# BreakoutBoard_RevA.net
KiCad netlist of a schematic drawn in EAGLE
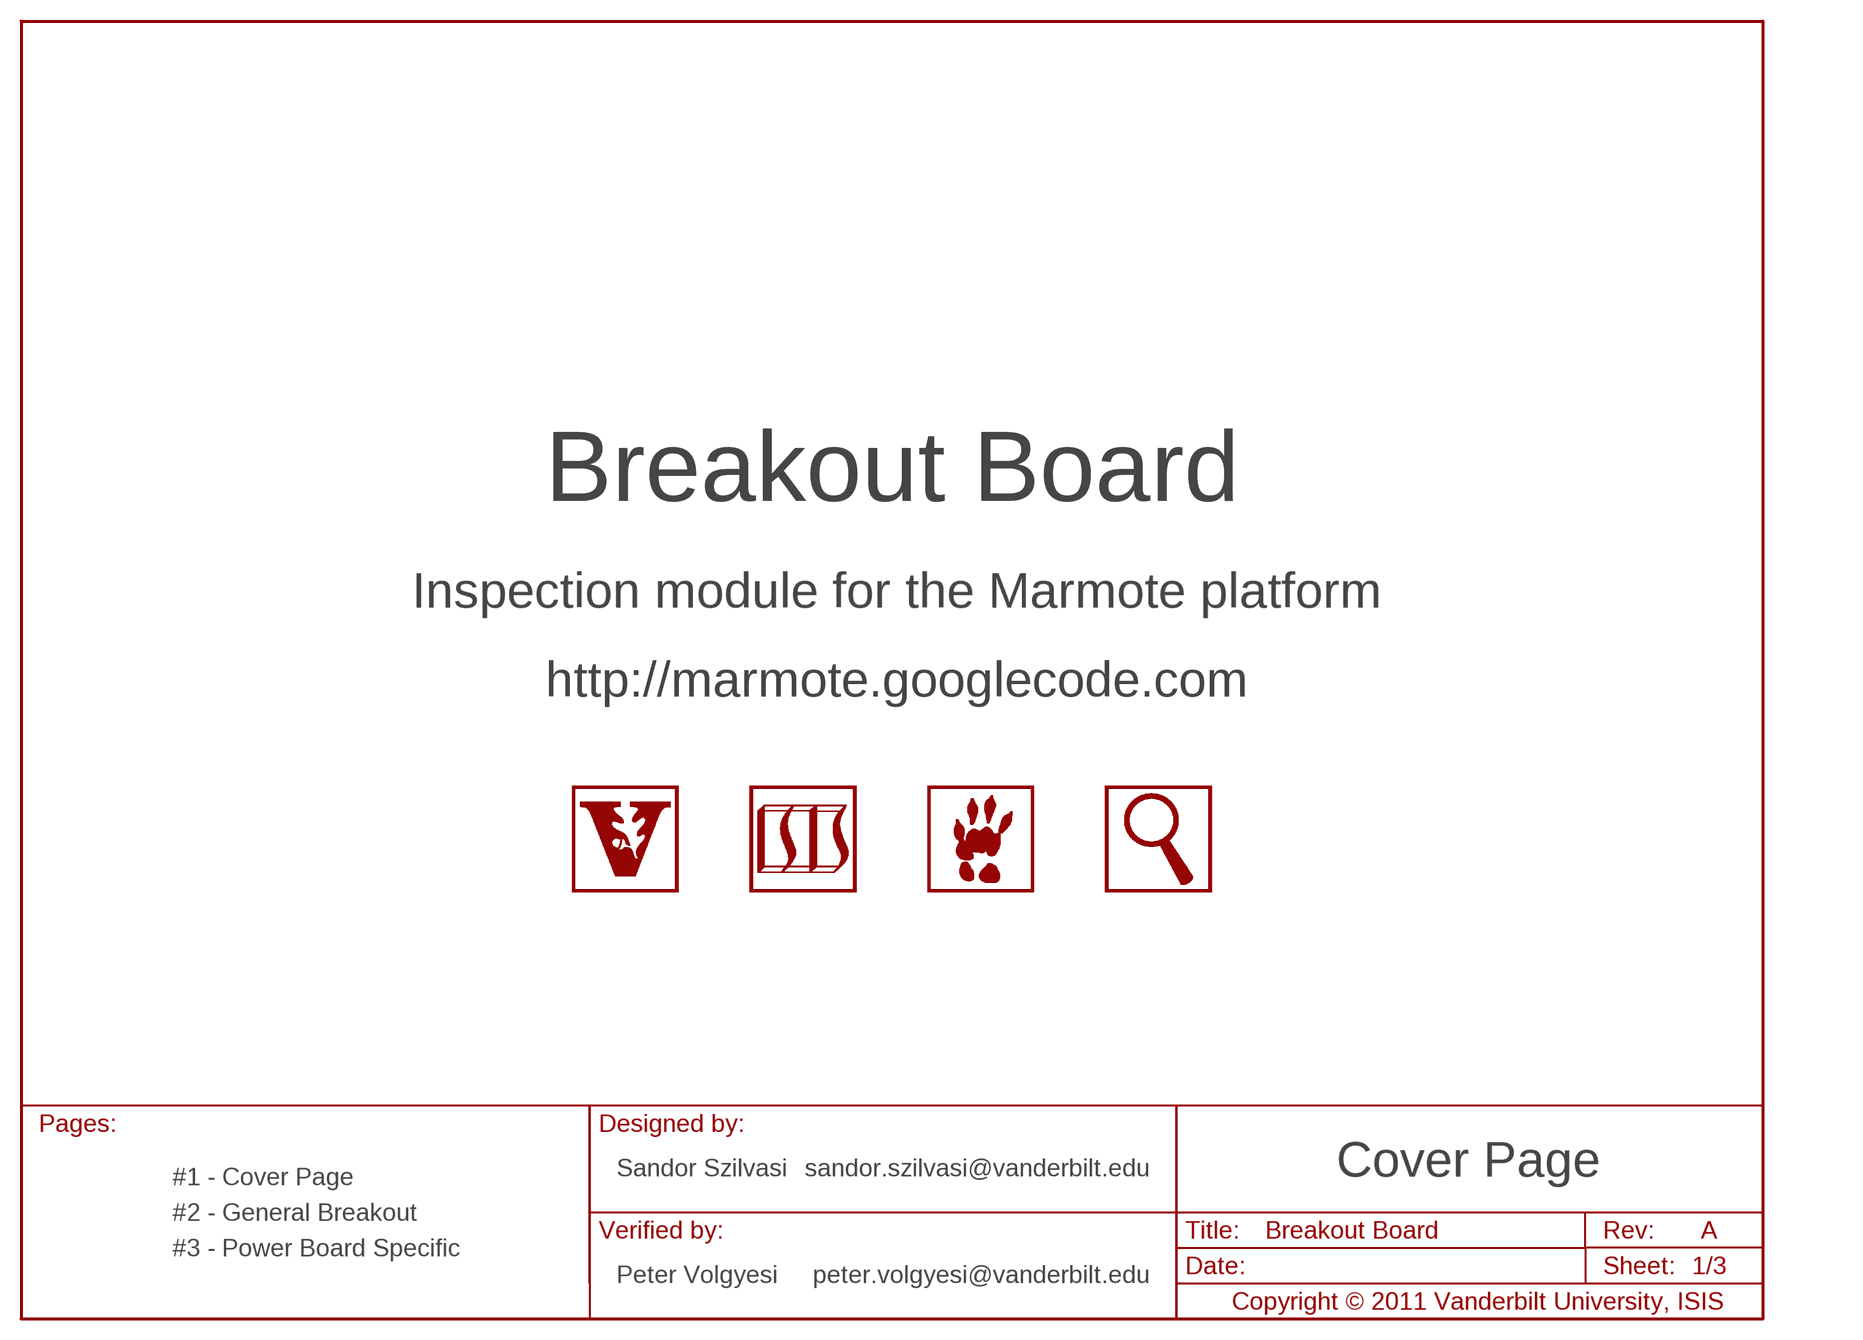
[diagram p0: schematic, sheet 1]
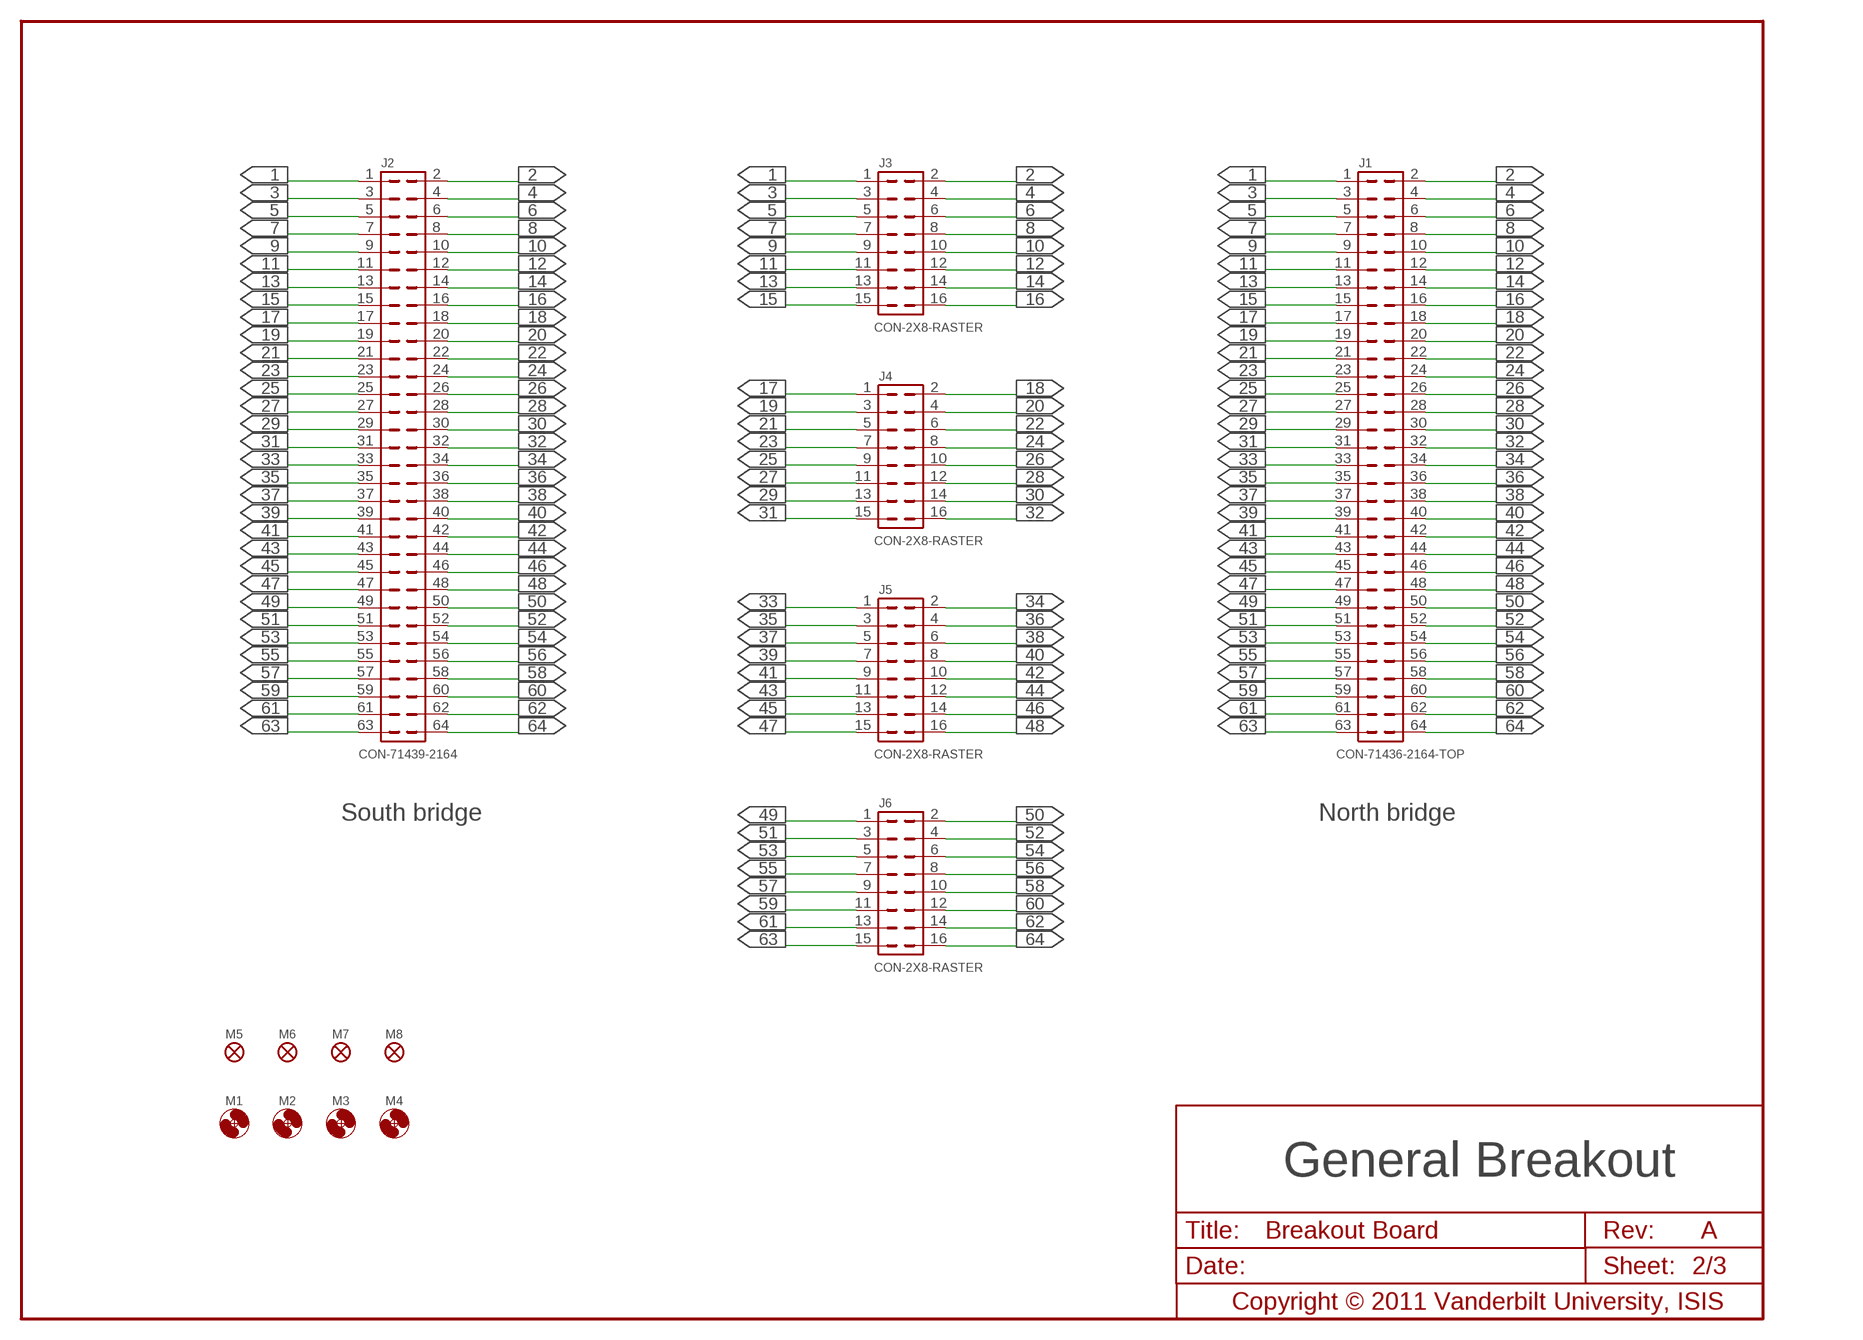
[diagram p1: schematic, sheet 2]
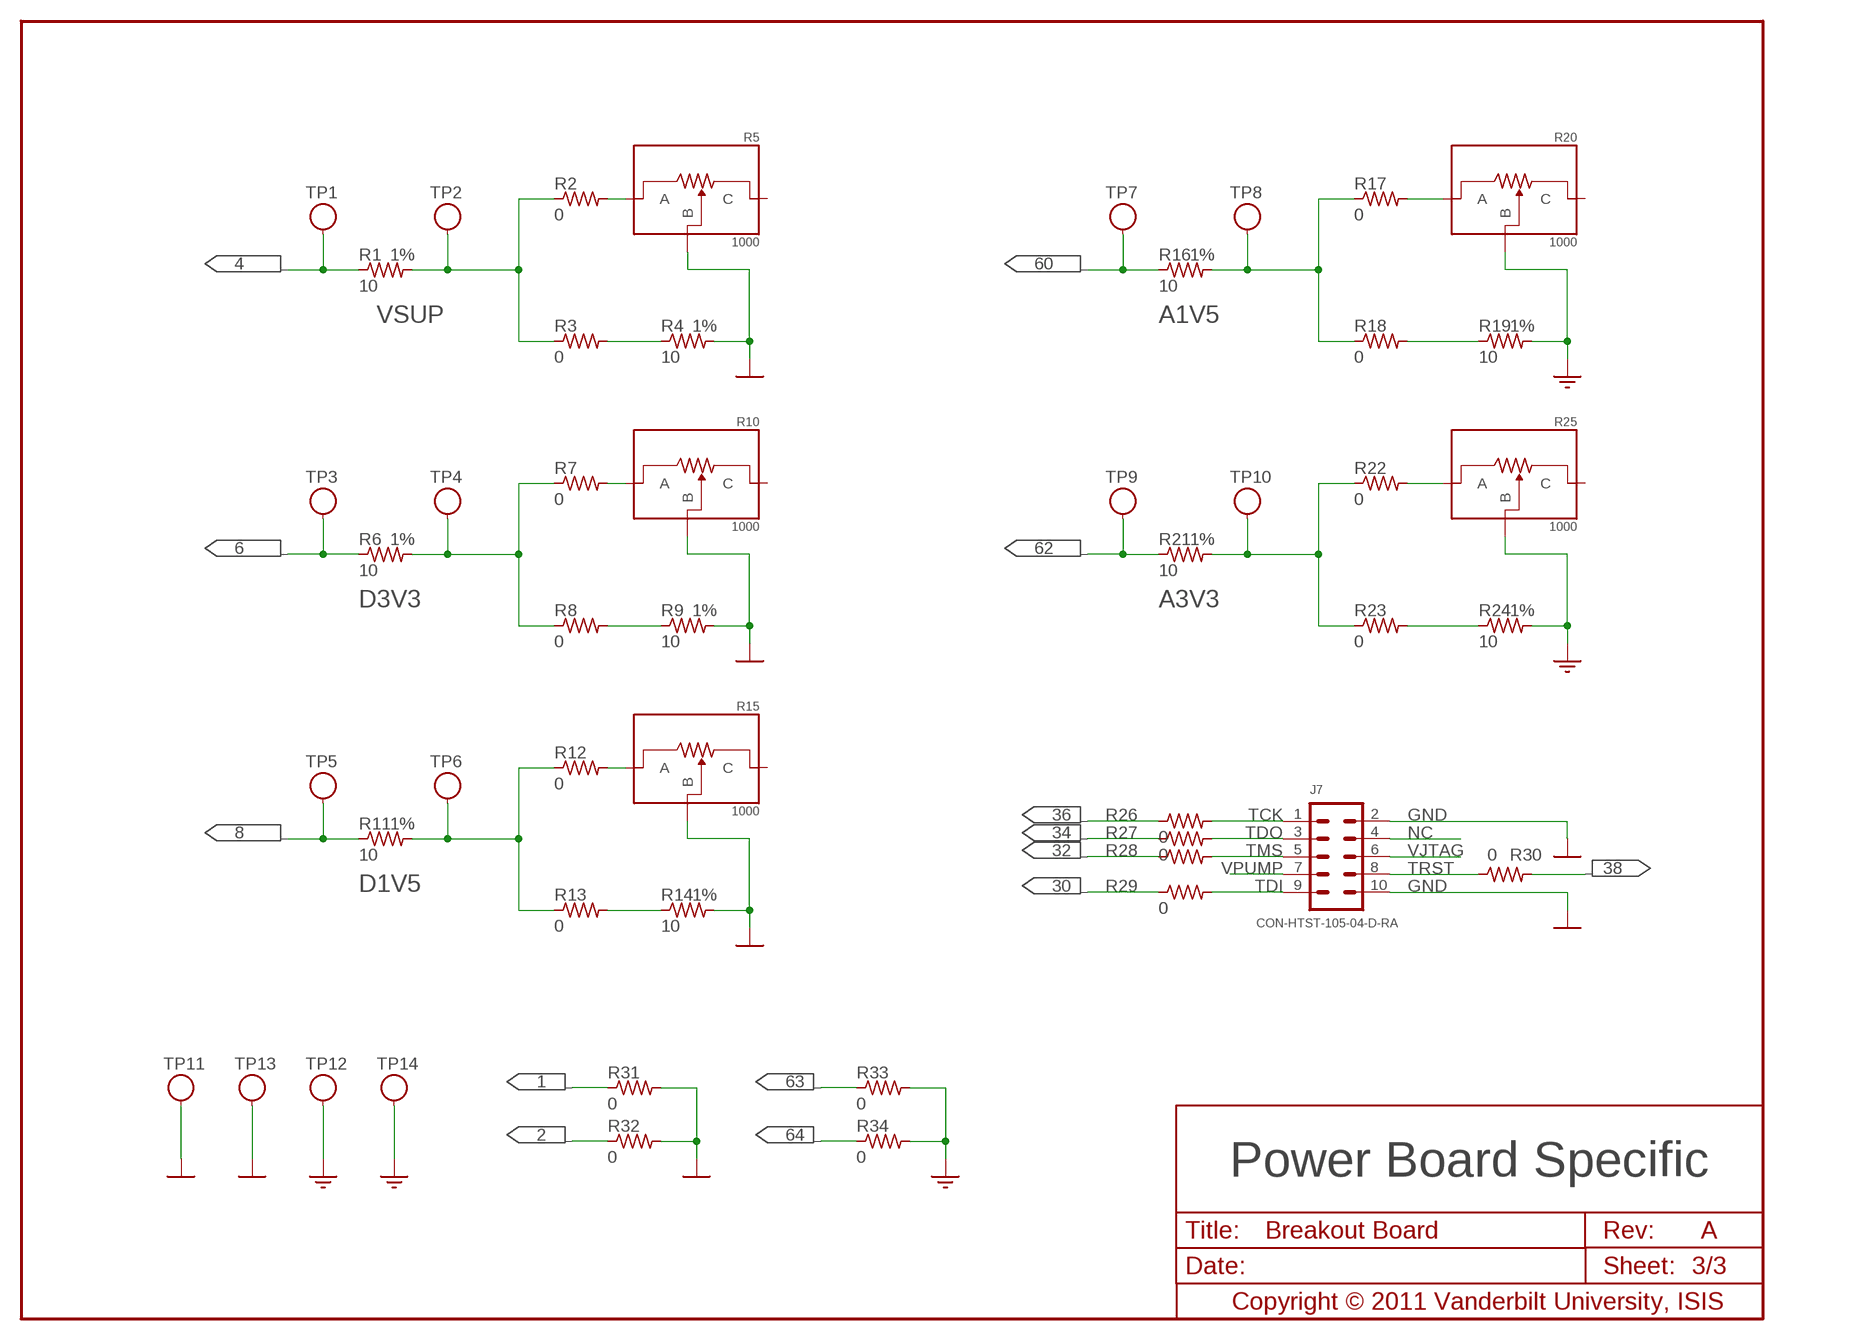
[diagram p2: schematic, sheet 3]

(export (version "E")
  (design (tool "Eeschema 10.0.6"))
  (components
    (comp (ref "J7")
      (value "CON-HTST-105-04-D-RA")
      (footprint "eagle-import:HTST-105-04-D-RA")
      (libsource (lib "eagle-import") (part "CON-HTST-105-04-D-RA"))
    )
    (comp (ref "R1")
      (value "10")
      (footprint "eagle-import:R0805")
      (fields (field (name "TOLERANCE") "1%"))
      (libsource (lib "eagle-import") (part "R0805"))
    )
    (comp (ref "R2")
      (value "0")
      (footprint "eagle-import:R0805")
      (libsource (lib "eagle-import") (part "R0805"))
    )
    (comp (ref "R3")
      (value "0")
      (footprint "eagle-import:R0805")
      (libsource (lib "eagle-import") (part "R0805"))
    )
    (comp (ref "R4")
      (value "10")
      (footprint "eagle-import:R0805")
      (fields (field (name "TOLERANCE") "1%"))
      (libsource (lib "eagle-import") (part "R0805"))
    )
    (comp (ref "R5")
      (value "1000")
      (footprint "eagle-import:TRIMMER-3MM")
      (fields (field (name "MF") "Panasonic - ECG") (field (name "MPN") "EVM-3WSX80B13 "))
      (libsource (lib "eagle-import") (part "TRIMMER"))
    )
    (comp (ref "R6")
      (value "10")
      (footprint "eagle-import:R0805")
      (fields (field (name "TOLERANCE") "1%"))
      (libsource (lib "eagle-import") (part "R0805"))
    )
    (comp (ref "R7")
      (value "0")
      (footprint "eagle-import:R0805")
      (libsource (lib "eagle-import") (part "R0805"))
    )
    (comp (ref "R8")
      (value "0")
      (footprint "eagle-import:R0805")
      (libsource (lib "eagle-import") (part "R0805"))
    )
    (comp (ref "R9")
      (value "10")
      (footprint "eagle-import:R0805")
      (fields (field (name "TOLERANCE") "1%"))
      (libsource (lib "eagle-import") (part "R0805"))
    )
    (comp (ref "R10")
      (value "1000")
      (footprint "eagle-import:TRIMMER-3MM")
      (fields (field (name "MF") "Panasonic - ECG") (field (name "MPN") "EVM-3WSX80B13 "))
      (libsource (lib "eagle-import") (part "TRIMMER"))
    )
    (comp (ref "R11")
      (value "10")
      (footprint "eagle-import:R0805")
      (fields (field (name "TOLERANCE") "1%"))
      (libsource (lib "eagle-import") (part "R0805"))
    )
    (comp (ref "R12")
      (value "0")
      (footprint "eagle-import:R0805")
      (libsource (lib "eagle-import") (part "R0805"))
    )
    (comp (ref "R13")
      (value "0")
      (footprint "eagle-import:R0805")
      (libsource (lib "eagle-import") (part "R0805"))
    )
    (comp (ref "R14")
      (value "10")
      (footprint "eagle-import:R0805")
      (fields (field (name "TOLERANCE") "1%"))
      (libsource (lib "eagle-import") (part "R0805"))
    )
    (comp (ref "R15")
      (value "1000")
      (footprint "eagle-import:TRIMMER-3MM")
      (fields (field (name "MF") "Panasonic - ECG") (field (name "MPN") "EVM-3WSX80B13 "))
      (libsource (lib "eagle-import") (part "TRIMMER"))
    )
    (comp (ref "R16")
      (value "10")
      (footprint "eagle-import:R0805")
      (fields (field (name "TOLERANCE") "1%"))
      (libsource (lib "eagle-import") (part "R0805"))
    )
    (comp (ref "R17")
      (value "0")
      (footprint "eagle-import:R0805")
      (libsource (lib "eagle-import") (part "R0805"))
    )
    (comp (ref "R18")
      (value "0")
      (footprint "eagle-import:R0805")
      (libsource (lib "eagle-import") (part "R0805"))
    )
    (comp (ref "R19")
      (value "10")
      (footprint "eagle-import:R0805")
      (fields (field (name "TOLERANCE") "1%"))
      (libsource (lib "eagle-import") (part "R0805"))
    )
    (comp (ref "R20")
      (value "1000")
      (footprint "eagle-import:TRIMMER-3MM")
      (fields (field (name "MF") "Panasonic - ECG") (field (name "MPN") "EVM-3WSX80B13 "))
      (libsource (lib "eagle-import") (part "TRIMMER"))
    )
    (comp (ref "R21")
      (value "10")
      (footprint "eagle-import:R0805")
      (fields (field (name "TOLERANCE") "1%"))
      (libsource (lib "eagle-import") (part "R0805"))
    )
    (comp (ref "R22")
      (value "0")
      (footprint "eagle-import:R0805")
      (libsource (lib "eagle-import") (part "R0805"))
    )
    (comp (ref "R23")
      (value "0")
      (footprint "eagle-import:R0805")
      (libsource (lib "eagle-import") (part "R0805"))
    )
    (comp (ref "R24")
      (value "10")
      (footprint "eagle-import:R0805")
      (fields (field (name "TOLERANCE") "1%"))
      (libsource (lib "eagle-import") (part "R0805"))
    )
    (comp (ref "R25")
      (value "1000")
      (footprint "eagle-import:TRIMMER-3MM")
      (fields (field (name "MF") "Panasonic - ECG") (field (name "MPN") "EVM-3WSX80B13 "))
      (libsource (lib "eagle-import") (part "TRIMMER"))
    )
    (comp (ref "R26")
      (value "0")
      (footprint "eagle-import:R0805")
      (libsource (lib "eagle-import") (part "R0805"))
    )
    (comp (ref "R27")
      (value "0")
      (footprint "eagle-import:R0805")
      (libsource (lib "eagle-import") (part "R0805"))
    )
    (comp (ref "R28")
      (value "0")
      (footprint "eagle-import:R0805")
      (libsource (lib "eagle-import") (part "R0805"))
    )
    (comp (ref "R29")
      (value "0")
      (footprint "eagle-import:R0805")
      (libsource (lib "eagle-import") (part "R0805"))
    )
    (comp (ref "R30")
      (value "0")
      (footprint "eagle-import:R0805")
      (libsource (lib "eagle-import") (part "R0805"))
    )
    (comp (ref "R31")
      (value "0")
      (footprint "eagle-import:R0805")
      (libsource (lib "eagle-import") (part "R0805"))
    )
    (comp (ref "R32")
      (value "0")
      (footprint "eagle-import:R0805")
      (libsource (lib "eagle-import") (part "R0805"))
    )
    (comp (ref "R33")
      (value "0")
      (footprint "eagle-import:R0805")
      (libsource (lib "eagle-import") (part "R0805"))
    )
    (comp (ref "R34")
      (value "0")
      (footprint "eagle-import:R0805")
      (libsource (lib "eagle-import") (part "R0805"))
    )
    (comp (ref "TP1")
      (value "TESTPOINT-BLUE")
      (footprint "eagle-import:TESTPOINT")
      (fields (field (name "MF") "Keystone") (field (name "MPN") "5122"))
      (libsource (lib "eagle-import") (part "TESTPOINT-BLUE"))
    )
    (comp (ref "TP2")
      (value "TESTPOINT-BLUE")
      (footprint "eagle-import:TESTPOINT")
      (fields (field (name "MF") "Keystone") (field (name "MPN") "5122"))
      (libsource (lib "eagle-import") (part "TESTPOINT-BLUE"))
    )
    (comp (ref "TP3")
      (value "TESTPOINT-BLUE")
      (footprint "eagle-import:TESTPOINT")
      (fields (field (name "MF") "Keystone") (field (name "MPN") "5122"))
      (libsource (lib "eagle-import") (part "TESTPOINT-BLUE"))
    )
    (comp (ref "TP4")
      (value "TESTPOINT-BLUE")
      (footprint "eagle-import:TESTPOINT")
      (fields (field (name "MF") "Keystone") (field (name "MPN") "5122"))
      (libsource (lib "eagle-import") (part "TESTPOINT-BLUE"))
    )
    (comp (ref "TP5")
      (value "TESTPOINT-BLUE")
      (footprint "eagle-import:TESTPOINT")
      (fields (field (name "MF") "Keystone") (field (name "MPN") "5122"))
      (libsource (lib "eagle-import") (part "TESTPOINT-BLUE"))
    )
    (comp (ref "TP6")
      (value "TESTPOINT-BLUE")
      (footprint "eagle-import:TESTPOINT")
      (fields (field (name "MF") "Keystone") (field (name "MPN") "5122"))
      (libsource (lib "eagle-import") (part "TESTPOINT-BLUE"))
    )
    (comp (ref "TP7")
      (value "TESTPOINT-GREEN")
      (footprint "eagle-import:TESTPOINT")
      (fields (field (name "MF") "Keystone") (field (name "MPN") "5121"))
      (libsource (lib "eagle-import") (part "TESTPOINT-GREEN"))
    )
    (comp (ref "TP8")
      (value "TESTPOINT-GREEN")
      (footprint "eagle-import:TESTPOINT")
      (fields (field (name "MF") "Keystone") (field (name "MPN") "5121"))
      (libsource (lib "eagle-import") (part "TESTPOINT-GREEN"))
    )
    (comp (ref "TP9")
      (value "TESTPOINT-GREEN")
      (footprint "eagle-import:TESTPOINT")
      (fields (field (name "MF") "Keystone") (field (name "MPN") "5121"))
      (libsource (lib "eagle-import") (part "TESTPOINT-GREEN"))
    )
    (comp (ref "TP10")
      (value "TESTPOINT-GREEN")
      (footprint "eagle-import:TESTPOINT")
      (fields (field (name "MF") "Keystone") (field (name "MPN") "5121"))
      (libsource (lib "eagle-import") (part "TESTPOINT-GREEN"))
    )
    (comp (ref "TP11")
      (value "TESTPOINT-YELLOW")
      (footprint "eagle-import:TESTPOINT")
      (fields (field (name "MF") "Keystone") (field (name "MPN") "5009"))
      (libsource (lib "eagle-import") (part "TESTPOINT-YELLOW"))
    )
    (comp (ref "TP12")
      (value "TESTPOINT-YELLOW")
      (footprint "eagle-import:TESTPOINT")
      (fields (field (name "MF") "Keystone") (field (name "MPN") "5009"))
      (libsource (lib "eagle-import") (part "TESTPOINT-YELLOW"))
    )
    (comp (ref "TP13")
      (value "TESTPOINT-YELLOW")
      (footprint "eagle-import:TESTPOINT")
      (fields (field (name "MF") "Keystone") (field (name "MPN") "5009"))
      (libsource (lib "eagle-import") (part "TESTPOINT-YELLOW"))
    )
    (comp (ref "TP14")
      (value "TESTPOINT-YELLOW")
      (footprint "eagle-import:TESTPOINT")
      (fields (field (name "MF") "Keystone") (field (name "MPN") "5009"))
      (libsource (lib "eagle-import") (part "TESTPOINT-YELLOW"))
    )
    (comp (ref "J1")
      (value "CON-71436-2164-TOP")
      (footprint "eagle-import:71436-XX64")
      (fields (field (name "MF") "Molex") (field (name "MPN") "71436-2164"))
      (libsource (lib "eagle-import") (part "CON-7143664-TOP-21"))
    )
    (comp (ref "J2")
      (value "CON-71439-2164")
      (footprint "eagle-import:71439-XX64-BOT")
      (fields (field (name "MF") "Molex") (field (name "MPN") "71439-2164"))
      (libsource (lib "eagle-import") (part "CON-7143964-21"))
    )
    (comp (ref "J3")
      (value "CON-2X8-RASTER")
      (footprint "eagle-import:2X16")
      (libsource (lib "eagle-import") (part "CON-2X8-RASTER"))
    )
    (comp (ref "J4")
      (value "CON-2X8-RASTER")
      (footprint "eagle-import:2X16")
      (libsource (lib "eagle-import") (part "CON-2X8-RASTER"))
    )
    (comp (ref "J5")
      (value "CON-2X8-RASTER")
      (footprint "eagle-import:2X16")
      (libsource (lib "eagle-import") (part "CON-2X8-RASTER"))
    )
    (comp (ref "J6")
      (value "CON-2X8-RASTER")
      (footprint "eagle-import:2X16")
      (libsource (lib "eagle-import") (part "CON-2X8-RASTER"))
    )
    (comp (ref "M1")
      (value "MOUNT-HOLE3.3")
      (footprint "eagle-import:3,3")
      (libsource (lib "eagle-import") (part "MOUNT-HOLE3.3"))
    )
    (comp (ref "M2")
      (value "MOUNT-HOLE3.3")
      (footprint "eagle-import:3,3")
      (libsource (lib "eagle-import") (part "MOUNT-HOLE3.3"))
    )
    (comp (ref "M3")
      (value "MOUNT-HOLE3.3")
      (footprint "eagle-import:3,3")
      (libsource (lib "eagle-import") (part "MOUNT-HOLE3.3"))
    )
    (comp (ref "M4")
      (value "MOUNT-HOLE3.3")
      (footprint "eagle-import:3,3")
      (libsource (lib "eagle-import") (part "MOUNT-HOLE3.3"))
    )
    (comp (ref "M5")
      (value "FIDUCIAL1X2")
      (footprint "eagle-import:FIDUCIAL-1X2")
      (libsource (lib "eagle-import") (part "FIDUCIAL1X2"))
    )
    (comp (ref "M6")
      (value "FIDUCIAL1X2")
      (footprint "eagle-import:FIDUCIAL-1X2")
      (libsource (lib "eagle-import") (part "FIDUCIAL1X2"))
    )
    (comp (ref "M7")
      (value "FIDUCIAL1X2")
      (footprint "eagle-import:FIDUCIAL-1X2")
      (libsource (lib "eagle-import") (part "FIDUCIAL1X2"))
    )
    (comp (ref "M8")
      (value "FIDUCIAL1X2")
      (footprint "eagle-import:FIDUCIAL-1X2")
      (libsource (lib "eagle-import") (part "FIDUCIAL1X2"))
    )
    (comp (ref "LOGO1")
      (value "LOGO-ISIS-600MIL-10MM-AU")
      (footprint "eagle-import:LOGO-ISIS-10MM-GOLD")
      (libsource (lib "eagle-import") (part "LOGO-ISIS-600MIL-10MM-AU"))
    )
    (comp (ref "LOGO2")
      (value "LOGO-VANDERBILT-600MIL-10MM-AU")
      (footprint "eagle-import:LOGO-VANDERBILT-10MM-GOLD")
      (libsource (lib "eagle-import") (part "LOGO-VANDERBILT-600MIL-10MM-AU"))
    )
    (comp (ref "LOGO3")
      (value "LOGO-MARMOTE-600MIL-10MM-AU")
      (footprint "eagle-import:LOGO-MARMOTE-10MM-GOLD")
      (libsource (lib "eagle-import") (part "LOGO-MARMOTE-600MIL-10MM-AU"))
    )
    (comp (ref "LOGO4")
      (value "LOGO-MAGNIFYING-GLASS-600MIL-10MM-AU")
      (footprint "eagle-import:LOGO-MAGNIFYING-GLASS-10MM-GOLD")
      (libsource (lib "eagle-import") (part "LOGO-MAGNIFYING-GLASS-600MIL-10MM-AU"))
    )
  )
  (nets
    (net (code "1") (name "1") (class "Default")
      (node (ref "J1") (pin "1") (pinfunction "1_1") (pintype "passive"))
      (node (ref "J2") (pin "1") (pinfunction "1_1") (pintype "passive"))
      (node (ref "J3") (pin "1") (pinfunction "1_1") (pintype "passive"))
      (node (ref "R31") (pin "1") (pinfunction "1_1") (pintype "passive"))
    )
    (net (code "2") (name "2") (class "Default")
      (node (ref "J1") (pin "2") (pinfunction "2_2") (pintype "passive"))
      (node (ref "J2") (pin "2") (pinfunction "2_2") (pintype "passive"))
      (node (ref "J3") (pin "2") (pinfunction "2_2") (pintype "passive"))
      (node (ref "R32") (pin "1") (pinfunction "1_1") (pintype "passive"))
    )
    (net (code "3") (name "3") (class "Default")
      (node (ref "J1") (pin "3") (pinfunction "3_3") (pintype "passive"))
      (node (ref "J2") (pin "3") (pinfunction "3_3") (pintype "passive"))
      (node (ref "J3") (pin "3") (pinfunction "3_3") (pintype "passive"))
    )
    (net (code "4") (name "4") (class "Default")
      (node (ref "J1") (pin "4") (pinfunction "4_4") (pintype "passive"))
      (node (ref "J2") (pin "4") (pinfunction "4_4") (pintype "passive"))
      (node (ref "J3") (pin "4") (pinfunction "4_4") (pintype "passive"))
      (node (ref "R1") (pin "1") (pinfunction "1_1") (pintype "passive"))
      (node (ref "TP1") (pin "1") (pinfunction "1_1") (pintype "power_in"))
    )
    (net (code "5") (name "5") (class "Default")
      (node (ref "J1") (pin "5") (pinfunction "5_5") (pintype "passive"))
      (node (ref "J2") (pin "5") (pinfunction "5_5") (pintype "passive"))
      (node (ref "J3") (pin "5") (pinfunction "5_5") (pintype "passive"))
    )
    (net (code "6") (name "6") (class "Default")
      (node (ref "J1") (pin "6") (pinfunction "6_6") (pintype "passive"))
      (node (ref "J2") (pin "6") (pinfunction "6_6") (pintype "passive"))
      (node (ref "J3") (pin "6") (pinfunction "6_6") (pintype "passive"))
      (node (ref "R6") (pin "1") (pinfunction "1_1") (pintype "passive"))
      (node (ref "TP3") (pin "1") (pinfunction "1_1") (pintype "power_in"))
    )
    (net (code "7") (name "7") (class "Default")
      (node (ref "J1") (pin "7") (pinfunction "7_7") (pintype "passive"))
      (node (ref "J2") (pin "7") (pinfunction "7_7") (pintype "passive"))
      (node (ref "J3") (pin "7") (pinfunction "7_7") (pintype "passive"))
    )
    (net (code "8") (name "8") (class "Default")
      (node (ref "J1") (pin "8") (pinfunction "8_8") (pintype "passive"))
      (node (ref "J2") (pin "8") (pinfunction "8_8") (pintype "passive"))
      (node (ref "J3") (pin "8") (pinfunction "8_8") (pintype "passive"))
      (node (ref "R11") (pin "1") (pinfunction "1_1") (pintype "passive"))
      (node (ref "TP5") (pin "1") (pinfunction "1_1") (pintype "power_in"))
    )
    (net (code "9") (name "9") (class "Default")
      (node (ref "J1") (pin "9") (pinfunction "9_9") (pintype "passive"))
      (node (ref "J2") (pin "9") (pinfunction "9_9") (pintype "passive"))
      (node (ref "J3") (pin "9") (pinfunction "9_9") (pintype "passive"))
    )
    (net (code "10") (name "10") (class "Default")
      (node (ref "J1") (pin "10") (pinfunction "10_10") (pintype "passive"))
      (node (ref "J2") (pin "10") (pinfunction "10_10") (pintype "passive"))
      (node (ref "J3") (pin "10") (pinfunction "10_10") (pintype "passive"))
    )
    (net (code "11") (name "11") (class "Default")
      (node (ref "J1") (pin "11") (pinfunction "11_11") (pintype "passive"))
      (node (ref "J2") (pin "11") (pinfunction "11_11") (pintype "passive"))
      (node (ref "J3") (pin "11") (pinfunction "11_11") (pintype "passive"))
    )
    (net (code "12") (name "12") (class "Default")
      (node (ref "J1") (pin "12") (pinfunction "12_12") (pintype "passive"))
      (node (ref "J2") (pin "12") (pinfunction "12_12") (pintype "passive"))
      (node (ref "J3") (pin "12") (pinfunction "12_12") (pintype "passive"))
    )
    (net (code "13") (name "13") (class "Default")
      (node (ref "J1") (pin "13") (pinfunction "13_13") (pintype "passive"))
      (node (ref "J2") (pin "13") (pinfunction "13_13") (pintype "passive"))
      (node (ref "J3") (pin "13") (pinfunction "13_13") (pintype "passive"))
    )
    (net (code "14") (name "14") (class "Default")
      (node (ref "J1") (pin "14") (pinfunction "14_14") (pintype "passive"))
      (node (ref "J2") (pin "14") (pinfunction "14_14") (pintype "passive"))
      (node (ref "J3") (pin "14") (pinfunction "14_14") (pintype "passive"))
    )
    (net (code "15") (name "15") (class "Default")
      (node (ref "J1") (pin "15") (pinfunction "15_15") (pintype "passive"))
      (node (ref "J2") (pin "15") (pinfunction "15_15") (pintype "passive"))
      (node (ref "J3") (pin "15") (pinfunction "15_15") (pintype "passive"))
    )
    (net (code "16") (name "16") (class "Default")
      (node (ref "J1") (pin "16") (pinfunction "16_16") (pintype "passive"))
      (node (ref "J2") (pin "16") (pinfunction "16_16") (pintype "passive"))
      (node (ref "J3") (pin "16") (pinfunction "16_16") (pintype "passive"))
    )
    (net (code "17") (name "17") (class "Default")
      (node (ref "J1") (pin "17") (pinfunction "17_17") (pintype "passive"))
      (node (ref "J2") (pin "17") (pinfunction "17_17") (pintype "passive"))
      (node (ref "J4") (pin "1") (pinfunction "1_1") (pintype "passive"))
    )
    (net (code "18") (name "18") (class "Default")
      (node (ref "J1") (pin "18") (pinfunction "18_18") (pintype "passive"))
      (node (ref "J2") (pin "18") (pinfunction "18_18") (pintype "passive"))
      (node (ref "J4") (pin "2") (pinfunction "2_2") (pintype "passive"))
    )
    (net (code "19") (name "19") (class "Default")
      (node (ref "J1") (pin "19") (pinfunction "19_19") (pintype "passive"))
      (node (ref "J2") (pin "19") (pinfunction "19_19") (pintype "passive"))
      (node (ref "J4") (pin "3") (pinfunction "3_3") (pintype "passive"))
    )
    (net (code "20") (name "20") (class "Default")
      (node (ref "J1") (pin "20") (pinfunction "20_20") (pintype "passive"))
      (node (ref "J2") (pin "20") (pinfunction "20_20") (pintype "passive"))
      (node (ref "J4") (pin "4") (pinfunction "4_4") (pintype "passive"))
    )
    (net (code "21") (name "21") (class "Default")
      (node (ref "J1") (pin "21") (pinfunction "21_21") (pintype "passive"))
      (node (ref "J2") (pin "21") (pinfunction "21_21") (pintype "passive"))
      (node (ref "J4") (pin "5") (pinfunction "5_5") (pintype "passive"))
    )
    (net (code "22") (name "22") (class "Default")
      (node (ref "J1") (pin "22") (pinfunction "22_22") (pintype "passive"))
      (node (ref "J2") (pin "22") (pinfunction "22_22") (pintype "passive"))
      (node (ref "J4") (pin "6") (pinfunction "6_6") (pintype "passive"))
    )
    (net (code "23") (name "23") (class "Default")
      (node (ref "J1") (pin "23") (pinfunction "23_23") (pintype "passive"))
      (node (ref "J2") (pin "23") (pinfunction "23_23") (pintype "passive"))
      (node (ref "J4") (pin "7") (pinfunction "7_7") (pintype "passive"))
    )
    (net (code "24") (name "24") (class "Default")
      (node (ref "J1") (pin "24") (pinfunction "24_24") (pintype "passive"))
      (node (ref "J2") (pin "24") (pinfunction "24_24") (pintype "passive"))
      (node (ref "J4") (pin "8") (pinfunction "8_8") (pintype "passive"))
    )
    (net (code "25") (name "25") (class "Default")
      (node (ref "J1") (pin "25") (pinfunction "25_25") (pintype "passive"))
      (node (ref "J2") (pin "25") (pinfunction "25_25") (pintype "passive"))
      (node (ref "J4") (pin "9") (pinfunction "9_9") (pintype "passive"))
    )
    (net (code "26") (name "26") (class "Default")
      (node (ref "J1") (pin "26") (pinfunction "26_26") (pintype "passive"))
      (node (ref "J2") (pin "26") (pinfunction "26_26") (pintype "passive"))
      (node (ref "J4") (pin "10") (pinfunction "10_10") (pintype "passive"))
    )
    (net (code "27") (name "27") (class "Default")
      (node (ref "J1") (pin "27") (pinfunction "27_27") (pintype "passive"))
      (node (ref "J2") (pin "27") (pinfunction "27_27") (pintype "passive"))
      (node (ref "J4") (pin "11") (pinfunction "11_11") (pintype "passive"))
    )
    (net (code "28") (name "28") (class "Default")
      (node (ref "J1") (pin "28") (pinfunction "28_28") (pintype "passive"))
      (node (ref "J2") (pin "28") (pinfunction "28_28") (pintype "passive"))
      (node (ref "J4") (pin "12") (pinfunction "12_12") (pintype "passive"))
    )
    (net (code "29") (name "29") (class "Default")
      (node (ref "J1") (pin "29") (pinfunction "29_29") (pintype "passive"))
      (node (ref "J2") (pin "29") (pinfunction "29_29") (pintype "passive"))
      (node (ref "J4") (pin "13") (pinfunction "13_13") (pintype "passive"))
    )
    (net (code "30") (name "30") (class "Default")
      (node (ref "J1") (pin "30") (pinfunction "30_30") (pintype "passive"))
      (node (ref "J2") (pin "30") (pinfunction "30_30") (pintype "passive"))
      (node (ref "J4") (pin "14") (pinfunction "14_14") (pintype "passive"))
      (node (ref "R29") (pin "1") (pinfunction "1_1") (pintype "passive"))
    )
    (net (code "31") (name "31") (class "Default")
      (node (ref "J1") (pin "31") (pinfunction "31_31") (pintype "passive"))
      (node (ref "J2") (pin "31") (pinfunction "31_31") (pintype "passive"))
      (node (ref "J4") (pin "15") (pinfunction "15_15") (pintype "passive"))
    )
    (net (code "32") (name "32") (class "Default")
      (node (ref "J1") (pin "32") (pinfunction "32_32") (pintype "passive"))
      (node (ref "J2") (pin "32") (pinfunction "32_32") (pintype "passive"))
      (node (ref "J4") (pin "16") (pinfunction "16_16") (pintype "passive"))
      (node (ref "R28") (pin "1") (pinfunction "1_1") (pintype "passive"))
    )
    (net (code "33") (name "33") (class "Default")
      (node (ref "J1") (pin "33") (pinfunction "33_33") (pintype "passive"))
      (node (ref "J2") (pin "33") (pinfunction "33_33") (pintype "passive"))
      (node (ref "J5") (pin "1") (pinfunction "1_1") (pintype "passive"))
    )
    (net (code "34") (name "34") (class "Default")
      (node (ref "J1") (pin "34") (pinfunction "34_34") (pintype "passive"))
      (node (ref "J2") (pin "34") (pinfunction "34_34") (pintype "passive"))
      (node (ref "J5") (pin "2") (pinfunction "2_2") (pintype "passive"))
      (node (ref "R27") (pin "1") (pinfunction "1_1") (pintype "passive"))
    )
    (net (code "35") (name "35") (class "Default")
      (node (ref "J1") (pin "35") (pinfunction "35_35") (pintype "passive"))
      (node (ref "J2") (pin "35") (pinfunction "35_35") (pintype "passive"))
      (node (ref "J5") (pin "3") (pinfunction "3_3") (pintype "passive"))
    )
    (net (code "36") (name "36") (class "Default")
      (node (ref "J1") (pin "36") (pinfunction "36_36") (pintype "passive"))
      (node (ref "J2") (pin "36") (pinfunction "36_36") (pintype "passive"))
      (node (ref "J5") (pin "4") (pinfunction "4_4") (pintype "passive"))
      (node (ref "R26") (pin "1") (pinfunction "1_1") (pintype "passive"))
    )
    (net (code "37") (name "37") (class "Default")
      (node (ref "J1") (pin "37") (pinfunction "37_37") (pintype "passive"))
      (node (ref "J2") (pin "37") (pinfunction "37_37") (pintype "passive"))
      (node (ref "J5") (pin "5") (pinfunction "5_5") (pintype "passive"))
    )
    (net (code "38") (name "38") (class "Default")
      (node (ref "J1") (pin "38") (pinfunction "38_38") (pintype "passive"))
      (node (ref "J2") (pin "38") (pinfunction "38_38") (pintype "passive"))
      (node (ref "J5") (pin "6") (pinfunction "6_6") (pintype "passive"))
      (node (ref "R30") (pin "2") (pinfunction "2_2") (pintype "passive"))
    )
    (net (code "39") (name "39") (class "Default")
      (node (ref "J1") (pin "39") (pinfunction "39_39") (pintype "passive"))
      (node (ref "J2") (pin "39") (pinfunction "39_39") (pintype "passive"))
      (node (ref "J5") (pin "7") (pinfunction "7_7") (pintype "passive"))
    )
    (net (code "40") (name "40") (class "Default")
      (node (ref "J1") (pin "40") (pinfunction "40_40") (pintype "passive"))
      (node (ref "J2") (pin "40") (pinfunction "40_40") (pintype "passive"))
      (node (ref "J5") (pin "8") (pinfunction "8_8") (pintype "passive"))
    )
    (net (code "41") (name "41") (class "Default")
      (node (ref "J1") (pin "41") (pinfunction "41_41") (pintype "passive"))
      (node (ref "J2") (pin "41") (pinfunction "41_41") (pintype "passive"))
      (node (ref "J5") (pin "9") (pinfunction "9_9") (pintype "passive"))
    )
    (net (code "42") (name "42") (class "Default")
      (node (ref "J1") (pin "42") (pinfunction "42_42") (pintype "passive"))
      (node (ref "J2") (pin "42") (pinfunction "42_42") (pintype "passive"))
      (node (ref "J5") (pin "10") (pinfunction "10_10") (pintype "passive"))
    )
    (net (code "43") (name "43") (class "Default")
      (node (ref "J1") (pin "43") (pinfunction "43_43") (pintype "passive"))
      (node (ref "J2") (pin "43") (pinfunction "43_43") (pintype "passive"))
      (node (ref "J5") (pin "11") (pinfunction "11_11") (pintype "passive"))
    )
    (net (code "44") (name "44") (class "Default")
      (node (ref "J1") (pin "44") (pinfunction "44_44") (pintype "passive"))
      (node (ref "J2") (pin "44") (pinfunction "44_44") (pintype "passive"))
      (node (ref "J5") (pin "12") (pinfunction "12_12") (pintype "passive"))
    )
    (net (code "45") (name "45") (class "Default")
      (node (ref "J1") (pin "45") (pinfunction "45_45") (pintype "passive"))
      (node (ref "J2") (pin "45") (pinfunction "45_45") (pintype "passive"))
      (node (ref "J5") (pin "13") (pinfunction "13_13") (pintype "passive"))
    )
    (net (code "46") (name "46") (class "Default")
      (node (ref "J1") (pin "46") (pinfunction "46_46") (pintype "passive"))
      (node (ref "J2") (pin "46") (pinfunction "46_46") (pintype "passive"))
      (node (ref "J5") (pin "14") (pinfunction "14_14") (pintype "passive"))
    )
    (net (code "47") (name "47") (class "Default")
      (node (ref "J1") (pin "47") (pinfunction "47_47") (pintype "passive"))
      (node (ref "J2") (pin "47") (pinfunction "47_47") (pintype "passive"))
      (node (ref "J5") (pin "15") (pinfunction "15_15") (pintype "passive"))
    )
    (net (code "48") (name "48") (class "Default")
      (node (ref "J1") (pin "48") (pinfunction "48_48") (pintype "passive"))
      (node (ref "J2") (pin "48") (pinfunction "48_48") (pintype "passive"))
      (node (ref "J5") (pin "16") (pinfunction "16_16") (pintype "passive"))
    )
    (net (code "49") (name "49") (class "Default")
      (node (ref "J1") (pin "49") (pinfunction "49_49") (pintype "passive"))
      (node (ref "J2") (pin "49") (pinfunction "49_49") (pintype "passive"))
      (node (ref "J6") (pin "1") (pinfunction "1_1") (pintype "passive"))
    )
    (net (code "50") (name "50") (class "Default")
      (node (ref "J1") (pin "50") (pinfunction "50_50") (pintype "passive"))
      (node (ref "J2") (pin "50") (pinfunction "50_50") (pintype "passive"))
      (node (ref "J6") (pin "2") (pinfunction "2_2") (pintype "passive"))
    )
    (net (code "51") (name "51") (class "Default")
      (node (ref "J1") (pin "51") (pinfunction "51_51") (pintype "passive"))
      (node (ref "J2") (pin "51") (pinfunction "51_51") (pintype "passive"))
      (node (ref "J6") (pin "3") (pinfunction "3_3") (pintype "passive"))
    )
    (net (code "52") (name "52") (class "Default")
      (node (ref "J1") (pin "52") (pinfunction "52_52") (pintype "passive"))
      (node (ref "J2") (pin "52") (pinfunction "52_52") (pintype "passive"))
      (node (ref "J6") (pin "4") (pinfunction "4_4") (pintype "passive"))
    )
    (net (code "53") (name "53") (class "Default")
      (node (ref "J1") (pin "53") (pinfunction "53_53") (pintype "passive"))
      (node (ref "J2") (pin "53") (pinfunction "53_53") (pintype "passive"))
      (node (ref "J6") (pin "5") (pinfunction "5_5") (pintype "passive"))
    )
    (net (code "54") (name "54") (class "Default")
      (node (ref "J1") (pin "54") (pinfunction "54_54") (pintype "passive"))
      (node (ref "J2") (pin "54") (pinfunction "54_54") (pintype "passive"))
      (node (ref "J6") (pin "6") (pinfunction "6_6") (pintype "passive"))
    )
    (net (code "55") (name "55") (class "Default")
      (node (ref "J1") (pin "55") (pinfunction "55_55") (pintype "passive"))
      (node (ref "J2") (pin "55") (pinfunction "55_55") (pintype "passive"))
      (node (ref "J6") (pin "7") (pinfunction "7_7") (pintype "passive"))
    )
    (net (code "56") (name "56") (class "Default")
      (node (ref "J1") (pin "56") (pinfunction "56_56") (pintype "passive"))
      (node (ref "J2") (pin "56") (pinfunction "56_56") (pintype "passive"))
      (node (ref "J6") (pin "8") (pinfunction "8_8") (pintype "passive"))
    )
    (net (code "57") (name "57") (class "Default")
      (node (ref "J1") (pin "57") (pinfunction "57_57") (pintype "passive"))
      (node (ref "J2") (pin "57") (pinfunction "57_57") (pintype "passive"))
      (node (ref "J6") (pin "9") (pinfunction "9_9") (pintype "passive"))
    )
    (net (code "58") (name "58") (class "Default")
      (node (ref "J1") (pin "58") (pinfunction "58_58") (pintype "passive"))
      (node (ref "J2") (pin "58") (pinfunction "58_58") (pintype "passive"))
      (node (ref "J6") (pin "10") (pinfunction "10_10") (pintype "passive"))
    )
    (net (code "59") (name "59") (class "Default")
      (node (ref "J1") (pin "59") (pinfunction "59_59") (pintype "passive"))
      (node (ref "J2") (pin "59") (pinfunction "59_59") (pintype "passive"))
      (node (ref "J6") (pin "11") (pinfunction "11_11") (pintype "passive"))
    )
    (net (code "60") (name "60") (class "Default")
      (node (ref "J1") (pin "60") (pinfunction "60_60") (pintype "passive"))
      (node (ref "J2") (pin "60") (pinfunction "60_60") (pintype "passive"))
      (node (ref "J6") (pin "12") (pinfunction "12_12") (pintype "passive"))
      (node (ref "R16") (pin "1") (pinfunction "1_1") (pintype "passive"))
      (node (ref "TP7") (pin "1") (pinfunction "1_1") (pintype "power_in"))
    )
    (net (code "61") (name "61") (class "Default")
      (node (ref "J1") (pin "61") (pinfunction "61_61") (pintype "passive"))
      (node (ref "J2") (pin "61") (pinfunction "61_61") (pintype "passive"))
      (node (ref "J6") (pin "13") (pinfunction "13_13") (pintype "passive"))
    )
    (net (code "62") (name "62") (class "Default")
      (node (ref "J1") (pin "62") (pinfunction "62_62") (pintype "passive"))
      (node (ref "J2") (pin "62") (pinfunction "62_62") (pintype "passive"))
      (node (ref "J6") (pin "14") (pinfunction "14_14") (pintype "passive"))
      (node (ref "R21") (pin "1") (pinfunction "1_1") (pintype "passive"))
      (node (ref "TP9") (pin "1") (pinfunction "1_1") (pintype "power_in"))
    )
    (net (code "63") (name "63") (class "Default")
      (node (ref "J1") (pin "63") (pinfunction "63_63") (pintype "passive"))
      (node (ref "J2") (pin "63") (pinfunction "63_63") (pintype "passive"))
      (node (ref "J6") (pin "15") (pinfunction "15_15") (pintype "passive"))
      (node (ref "R33") (pin "1") (pinfunction "1_1") (pintype "passive"))
    )
    (net (code "64") (name "64") (class "Default")
      (node (ref "J1") (pin "64") (pinfunction "64_64") (pintype "passive"))
      (node (ref "J2") (pin "64") (pinfunction "64_64") (pintype "passive"))
      (node (ref "J6") (pin "16") (pinfunction "16_16") (pintype "passive"))
      (node (ref "R34") (pin "1") (pinfunction "1_1") (pintype "passive"))
    )
    (net (code "65") (name "AGND") (class "Default")
      (node (ref "R19") (pin "2") (pinfunction "2_2") (pintype "passive"))
      (node (ref "R20") (pin "2") (pinfunction "B_2") (pintype "passive"))
      (node (ref "R24") (pin "2") (pinfunction "2_2") (pintype "passive"))
      (node (ref "R25") (pin "2") (pinfunction "B_2") (pintype "passive"))
      (node (ref "R33") (pin "2") (pinfunction "2_2") (pintype "passive"))
      (node (ref "R34") (pin "2") (pinfunction "2_2") (pintype "passive"))
      (node (ref "TP12") (pin "1") (pinfunction "1_1") (pintype "power_in"))
      (node (ref "TP14") (pin "1") (pinfunction "1_1") (pintype "power_in"))
    )
    (net (code "66") (name "DGND") (class "Default")
      (node (ref "J7") (pin "10") (pinfunction "10_10") (pintype "passive"))
      (node (ref "J7") (pin "2") (pinfunction "2_2") (pintype "passive"))
      (node (ref "R10") (pin "2") (pinfunction "B_2") (pintype "passive"))
      (node (ref "R14") (pin "2") (pinfunction "2_2") (pintype "passive"))
      (node (ref "R15") (pin "2") (pinfunction "B_2") (pintype "passive"))
      (node (ref "R31") (pin "2") (pinfunction "2_2") (pintype "passive"))
      (node (ref "R32") (pin "2") (pinfunction "2_2") (pintype "passive"))
      (node (ref "R4") (pin "2") (pinfunction "2_2") (pintype "passive"))
      (node (ref "R5") (pin "2") (pinfunction "B_2") (pintype "passive"))
      (node (ref "R9") (pin "2") (pinfunction "2_2") (pintype "passive"))
      (node (ref "TP11") (pin "1") (pinfunction "1_1") (pintype "power_in"))
      (node (ref "TP13") (pin "1") (pinfunction "1_1") (pintype "power_in"))
    )
    (net (code "67") (name "NC") (class "Default")
      (node (ref "J7") (pin "4") (pinfunction "4_4") (pintype "passive"))
    )
    (net (code "68") (name "Net-(R1-Pad2)") (class "Default")
      (node (ref "R1") (pin "2") (pinfunction "2_2") (pintype "passive"))
      (node (ref "R2") (pin "1") (pinfunction "1_1") (pintype "passive"))
      (node (ref "R3") (pin "1") (pinfunction "1_1") (pintype "passive"))
      (node (ref "TP2") (pin "1") (pinfunction "1_1") (pintype "power_in"))
    )
    (net (code "69") (name "Net-(R3-Pad2)") (class "Default")
      (node (ref "R3") (pin "2") (pinfunction "2_2") (pintype "passive"))
      (node (ref "R4") (pin "1") (pinfunction "1_1") (pintype "passive"))
    )
    (net (code "70") (name "Net-(R5-A)") (class "Default")
      (node (ref "R2") (pin "2") (pinfunction "2_2") (pintype "passive"))
      (node (ref "R5") (pin "1") (pinfunction "A_1") (pintype "passive"))
    )
    (net (code "71") (name "Net-(R6-Pad2)") (class "Default")
      (node (ref "R6") (pin "2") (pinfunction "2_2") (pintype "passive"))
      (node (ref "R7") (pin "1") (pinfunction "1_1") (pintype "passive"))
      (node (ref "R8") (pin "1") (pinfunction "1_1") (pintype "passive"))
      (node (ref "TP4") (pin "1") (pinfunction "1_1") (pintype "power_in"))
    )
    (net (code "72") (name "Net-(R8-Pad2)") (class "Default")
      (node (ref "R8") (pin "2") (pinfunction "2_2") (pintype "passive"))
      (node (ref "R9") (pin "1") (pinfunction "1_1") (pintype "passive"))
    )
    (net (code "73") (name "Net-(R10-A)") (class "Default")
      (node (ref "R10") (pin "1") (pinfunction "A_1") (pintype "passive"))
      (node (ref "R7") (pin "2") (pinfunction "2_2") (pintype "passive"))
    )
    (net (code "74") (name "Net-(R11-Pad2)") (class "Default")
      (node (ref "R11") (pin "2") (pinfunction "2_2") (pintype "passive"))
      (node (ref "R12") (pin "1") (pinfunction "1_1") (pintype "passive"))
      (node (ref "R13") (pin "1") (pinfunction "1_1") (pintype "passive"))
      (node (ref "TP6") (pin "1") (pinfunction "1_1") (pintype "power_in"))
    )
    (net (code "75") (name "Net-(R13-Pad2)") (class "Default")
      (node (ref "R13") (pin "2") (pinfunction "2_2") (pintype "passive"))
      (node (ref "R14") (pin "1") (pinfunction "1_1") (pintype "passive"))
    )
    (net (code "76") (name "Net-(R15-A)") (class "Default")
      (node (ref "R12") (pin "2") (pinfunction "2_2") (pintype "passive"))
      (node (ref "R15") (pin "1") (pinfunction "A_1") (pintype "passive"))
    )
    (net (code "77") (name "Net-(R16-Pad2)") (class "Default")
      (node (ref "R16") (pin "2") (pinfunction "2_2") (pintype "passive"))
      (node (ref "R17") (pin "1") (pinfunction "1_1") (pintype "passive"))
      (node (ref "R18") (pin "1") (pinfunction "1_1") (pintype "passive"))
      (node (ref "TP8") (pin "1") (pinfunction "1_1") (pintype "power_in"))
    )
    (net (code "78") (name "Net-(R18-Pad2)") (class "Default")
      (node (ref "R18") (pin "2") (pinfunction "2_2") (pintype "passive"))
      (node (ref "R19") (pin "1") (pinfunction "1_1") (pintype "passive"))
    )
    (net (code "79") (name "Net-(R20-A)") (class "Default")
      (node (ref "R17") (pin "2") (pinfunction "2_2") (pintype "passive"))
      (node (ref "R20") (pin "1") (pinfunction "A_1") (pintype "passive"))
    )
    (net (code "80") (name "Net-(R21-Pad2)") (class "Default")
      (node (ref "R21") (pin "2") (pinfunction "2_2") (pintype "passive"))
      (node (ref "R22") (pin "1") (pinfunction "1_1") (pintype "passive"))
      (node (ref "R23") (pin "1") (pinfunction "1_1") (pintype "passive"))
      (node (ref "TP10") (pin "1") (pinfunction "1_1") (pintype "power_in"))
    )
    (net (code "81") (name "Net-(R23-Pad2)") (class "Default")
      (node (ref "R23") (pin "2") (pinfunction "2_2") (pintype "passive"))
      (node (ref "R24") (pin "1") (pinfunction "1_1") (pintype "passive"))
    )
    (net (code "82") (name "Net-(R25-A)") (class "Default")
      (node (ref "R22") (pin "2") (pinfunction "2_2") (pintype "passive"))
      (node (ref "R25") (pin "1") (pinfunction "A_1") (pintype "passive"))
    )
    (net (code "83") (name "TCK") (class "Default")
      (node (ref "J7") (pin "1") (pinfunction "1_1") (pintype "passive"))
      (node (ref "R26") (pin "2") (pinfunction "2_2") (pintype "passive"))
    )
    (net (code "84") (name "TDI") (class "Default")
      (node (ref "J7") (pin "9") (pinfunction "9_9") (pintype "passive"))
      (node (ref "R29") (pin "2") (pinfunction "2_2") (pintype "passive"))
    )
    (net (code "85") (name "TDO") (class "Default")
      (node (ref "J7") (pin "3") (pinfunction "3_3") (pintype "passive"))
      (node (ref "R27") (pin "2") (pinfunction "2_2") (pintype "passive"))
    )
    (net (code "86") (name "TMS") (class "Default")
      (node (ref "J7") (pin "5") (pinfunction "5_5") (pintype "passive"))
      (node (ref "R28") (pin "2") (pinfunction "2_2") (pintype "passive"))
    )
    (net (code "87") (name "TRST") (class "Default")
      (node (ref "J7") (pin "8") (pinfunction "8_8") (pintype "passive"))
      (node (ref "R30") (pin "1") (pinfunction "1_1") (pintype "passive"))
    )
    (net (code "88") (name "VJTAG") (class "Default")
      (node (ref "J7") (pin "6") (pinfunction "6_6") (pintype "passive"))
    )
    (net (code "89") (name "VPUMP") (class "Default")
      (node (ref "J7") (pin "7") (pinfunction "7_7") (pintype "passive"))
    )
    (net (code "90") (name "unconnected-(R5-C-Pad3)") (class "Default")
      (node (ref "R5") (pin "3") (pinfunction "C_3") (pintype "passive"))
    )
    (net (code "91") (name "unconnected-(R10-C-Pad3)") (class "Default")
      (node (ref "R10") (pin "3") (pinfunction "C_3") (pintype "passive"))
    )
    (net (code "92") (name "unconnected-(R15-C-Pad3)") (class "Default")
      (node (ref "R15") (pin "3") (pinfunction "C_3") (pintype "passive"))
    )
    (net (code "93") (name "unconnected-(R20-C-Pad3)") (class "Default")
      (node (ref "R20") (pin "3") (pinfunction "C_3") (pintype "passive"))
    )
    (net (code "94") (name "unconnected-(R25-C-Pad3)") (class "Default")
      (node (ref "R25") (pin "3") (pinfunction "C_3") (pintype "passive"))
    )
  )
)
